# USB_Type_C_Connector_ESD.net
KiCad netlist of a schematic drawn in Altium Designer
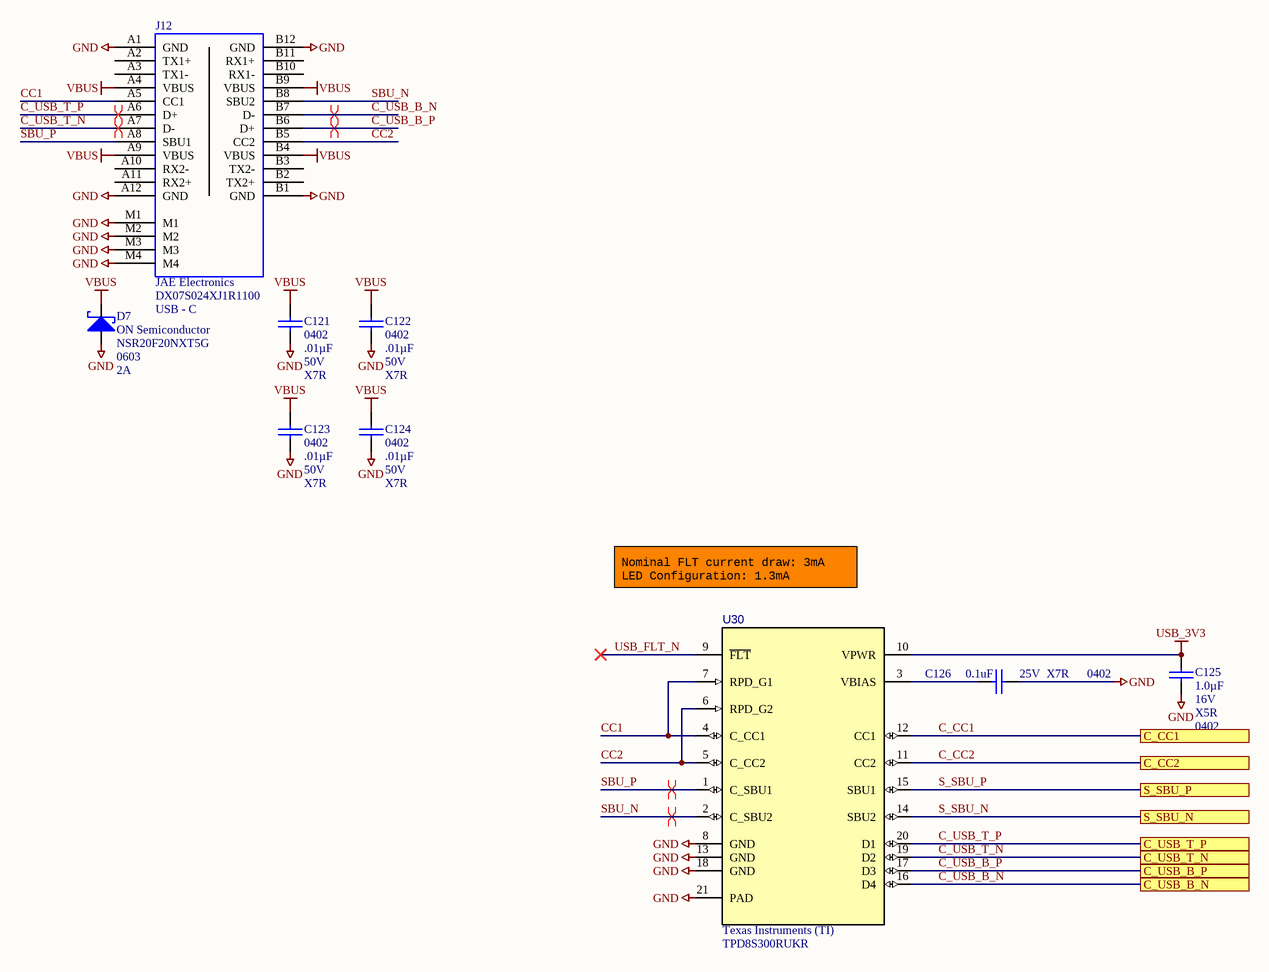
[diagram p0: USB Type C Connector ESD.SchDoc]

(export (version "E")
  (design (tool "Eeschema 10.0.6"))
  (components
    (comp (ref "C121")
      (value "10000pF")
      (footprint "C_0402")
      (description "CAP CERAMIC .01UF 50V X7R 0402")
      (fields
        (field (name "MANUFACTURER") "Murata Electronics North America")
        (field (name "MANUFACTURER PART NUMBER") "GRM155R71H103KA88D")
        (field (name "PACKAGE / CASE") "0402")
        (field (name "CAPACITANCE") ".01µF")
        (field (name "VOLTAGE - RATED") "50V")
        (field (name "TEMPERATURE COEFFICIENT") "X7R")
      )
      (libsource (lib "Main LibraryX") (part "C_0402_10000PF_50V"))
    )
    (comp (ref "C122")
      (value "10000pF")
      (footprint "C_0402")
      (description "CAP CERAMIC .01UF 50V X7R 0402")
      (fields
        (field (name "MANUFACTURER") "Murata Electronics North America")
        (field (name "MANUFACTURER PART NUMBER") "GRM155R71H103KA88D")
        (field (name "PACKAGE / CASE") "0402")
        (field (name "CAPACITANCE") ".01µF")
        (field (name "VOLTAGE - RATED") "50V")
        (field (name "TEMPERATURE COEFFICIENT") "X7R")
      )
      (libsource (lib "Main LibraryX") (part "C_0402_10000PF_50V"))
    )
    (comp (ref "C123")
      (value "10000pF")
      (footprint "C_0402")
      (description "CAP CERAMIC .01UF 50V X7R 0402")
      (fields
        (field (name "MANUFACTURER") "Murata Electronics North America")
        (field (name "MANUFACTURER PART NUMBER") "GRM155R71H103KA88D")
        (field (name "PACKAGE / CASE") "0402")
        (field (name "CAPACITANCE") ".01µF")
        (field (name "VOLTAGE - RATED") "50V")
        (field (name "TEMPERATURE COEFFICIENT") "X7R")
      )
      (libsource (lib "Main LibraryX") (part "C_0402_10000PF_50V"))
    )
    (comp (ref "C124")
      (value "10000pF")
      (footprint "C_0402")
      (description "CAP CERAMIC .01UF 50V X7R 0402")
      (fields
        (field (name "MANUFACTURER") "Murata Electronics North America")
        (field (name "MANUFACTURER PART NUMBER") "GRM155R71H103KA88D")
        (field (name "PACKAGE / CASE") "0402")
        (field (name "CAPACITANCE") ".01µF")
        (field (name "VOLTAGE - RATED") "50V")
        (field (name "TEMPERATURE COEFFICIENT") "X7R")
      )
      (libsource (lib "Main LibraryX") (part "C_0402_10000PF_50V"))
    )
    (comp (ref "C125")
      (value "1.0uF")
      (footprint "C_0402")
      (description "CAP CER 1.0UF 16V X5R 0402")
      (fields
        (field (name "TOLERANCE") "10%")
        (field (name "CAPACITANCE") "1.0µF")
        (field (name "VOLTAGE - RATED") "16V")
        (field (name "TEMPERATURE COEFFICIENT") "X5R")
        (field (name "PACKAGE / CASE") "0402")
        (field (name "VOLTAGE") "16V")
      )
      (libsource (lib "Main LibraryX") (part "C_0402_1.0UF_16V"))
    )
    (comp (ref "C126")
      (value "C_0402_0.1UF_25V")
      (footprint "C_0402")
      (description "CAP CER 0.1UF 25V X6S 0402")
      (fields
        (field (name "TOLERANCE") "10%")
        (field (name "CAPACITANCE") "0.1uF")
        (field (name "VOLTAGE - RATED") "25V")
        (field (name "TEMPERATURE COEFFICIENT") "X7R")
        (field (name "PACKAGE / CASE") "0402")
      )
      (libsource (lib "Cospan Design") (part "C_0402_0.1UF_25V"))
    )
    (comp (ref "D7")
      (value "D_SCHOTT_30V_2A_XDFN")
      (footprint "DSN2_0603")
      (description "Diode Schottky 30V 2A (DC) Surface Mount 2-DSN (1.6x.80)")
      (fields
        (field (name "MANUFACTURER") "ON Semiconductor")
        (field (name "MANUFACTURER PART NUMBER") "NSR20F20NXT5G")
        (field (name "CASE/PACKAGE") "0603")
        (field (name "AVERAGE RECTIFIED CURRENT") "2A")
      )
      (libsource (lib "Cospan Design") (part "D_SCHOTT_30V_2A_XDFN"))
    )
    (comp (ref "J12")
      (value "J_DX07S024XJ1R1100")
      (footprint "DX07S024XJ1R1100")
      (description "CONN RCPT USB C TOP MNT HYBRID")
      (fields
        (field (name "MANUFACTURER") "JAE Electronics")
        (field (name "MANUFACTURER PART NUMBER") "DX07S024XJ1R1100")
        (field (name "CONNECTOR TYPE") "USB - C")
      )
      (libsource (lib "Cospan Design") (part "J_DX07S024XJ1R1100"))
    )
    (comp (ref "U30")
      (value "U_TPD8S300RUK")
      (footprint "RUK0020B")
      (fields
        (field (name "MANUFACTURER") "Texas Instruments (TI)")
        (field (name "MANUFACTURER PART NUMBER") "TPD8S300RUKR")
      )
      (libsource (lib "Cospan Design") (part "U_TPD8S300RUK"))
    )
  )
  (nets
    (net (code "1") (name "/CC1") (class "Default")
      (node (ref "J12") (pin "A5") (pinfunction "CC1_A5") (pintype "passive"))
      (node (ref "U30") (pin "4") (pinfunction "C_CC1_4") (pintype "bidirectional"))
      (node (ref "U30") (pin "7") (pinfunction "RPD_G1_7") (pintype "input"))
    )
    (net (code "2") (name "/CC2") (class "Default")
      (node (ref "J12") (pin "B5") (pinfunction "CC2_B5") (pintype "passive"))
      (node (ref "U30") (pin "5") (pinfunction "C_CC2_5") (pintype "bidirectional"))
      (node (ref "U30") (pin "6") (pinfunction "RPD_G2_6") (pintype "input"))
    )
    (net (code "3") (name "/C_CC1") (class "Default")
      (node (ref "U30") (pin "12") (pinfunction "CC1_12") (pintype "bidirectional"))
    )
    (net (code "4") (name "/C_CC2") (class "Default")
      (node (ref "U30") (pin "11") (pinfunction "CC2_11") (pintype "bidirectional"))
    )
    (net (code "5") (name "/C_USB_B_N") (class "Default")
      (node (ref "J12") (pin "B7") (pinfunction "D-_B7") (pintype "passive"))
      (node (ref "U30") (pin "16") (pinfunction "D4_16") (pintype "bidirectional"))
    )
    (net (code "6") (name "/C_USB_B_P") (class "Default")
      (node (ref "J12") (pin "B6") (pinfunction "D+_B6") (pintype "passive"))
      (node (ref "U30") (pin "17") (pinfunction "D3_17") (pintype "bidirectional"))
    )
    (net (code "7") (name "/C_USB_T_N") (class "Default")
      (node (ref "J12") (pin "A7") (pinfunction "D-_A7") (pintype "passive"))
      (node (ref "U30") (pin "19") (pinfunction "D2_19") (pintype "bidirectional"))
    )
    (net (code "8") (name "/C_USB_T_P") (class "Default")
      (node (ref "J12") (pin "A6") (pinfunction "D+_A6") (pintype "passive"))
      (node (ref "U30") (pin "20") (pinfunction "D1_20") (pintype "bidirectional"))
    )
    (net (code "9") (name "/SBU_N") (class "Default")
      (node (ref "J12") (pin "B8") (pinfunction "SBU2_B8") (pintype "passive"))
      (node (ref "U30") (pin "2") (pinfunction "C_SBU2_2") (pintype "bidirectional"))
    )
    (net (code "10") (name "/SBU_P") (class "Default")
      (node (ref "J12") (pin "A8") (pinfunction "SBU1_A8") (pintype "passive"))
      (node (ref "U30") (pin "1") (pinfunction "C_SBU1_1") (pintype "bidirectional"))
    )
    (net (code "11") (name "/S_SBU_N") (class "Default")
      (node (ref "U30") (pin "14") (pinfunction "SBU2_14") (pintype "bidirectional"))
    )
    (net (code "12") (name "/S_SBU_P") (class "Default")
      (node (ref "U30") (pin "15") (pinfunction "SBU1_15") (pintype "bidirectional"))
    )
    (net (code "13") (name "/USB_FLT_N") (class "Default")
      (node (ref "U30") (pin "9") (pinfunction "FLT_9") (pintype "open_collector+no_connect"))
    )
    (net (code "14") (name "GND") (class "Default")
      (node (ref "C121") (pin "1") (pinfunction "1_1") (pintype "passive"))
      (node (ref "C122") (pin "1") (pinfunction "1_1") (pintype "passive"))
      (node (ref "C123") (pin "1") (pinfunction "1_1") (pintype "passive"))
      (node (ref "C124") (pin "1") (pinfunction "1_1") (pintype "passive"))
      (node (ref "C125") (pin "1") (pinfunction "1_1") (pintype "passive"))
      (node (ref "C126") (pin "1") (pinfunction "1_1") (pintype "passive"))
      (node (ref "D7") (pin "2") (pinfunction "A_2") (pintype "passive"))
      (node (ref "J12") (pin "A1") (pinfunction "GND_A1") (pintype "passive"))
      (node (ref "J12") (pin "A12") (pinfunction "GND_A12") (pintype "passive"))
      (node (ref "J12") (pin "B1") (pinfunction "GND_B1") (pintype "passive"))
      (node (ref "J12") (pin "B12") (pinfunction "GND_B12") (pintype "passive"))
      (node (ref "J12") (pin "M1") (pinfunction "M1_M1") (pintype "passive"))
      (node (ref "J12") (pin "M2") (pinfunction "M2_M2") (pintype "passive"))
      (node (ref "J12") (pin "M3") (pinfunction "M3_M3") (pintype "passive"))
      (node (ref "J12") (pin "M4") (pinfunction "M4_M4") (pintype "passive"))
      (node (ref "U30") (pin "13") (pinfunction "GND_13") (pintype "power_in"))
      (node (ref "U30") (pin "18") (pinfunction "GND_18") (pintype "power_in"))
      (node (ref "U30") (pin "21") (pinfunction "PAD_21") (pintype "power_in"))
      (node (ref "U30") (pin "8") (pinfunction "GND_8") (pintype "power_in"))
    )
    (net (code "15") (name "Net-(U30-VBIAS)") (class "Default")
      (node (ref "C126") (pin "2") (pinfunction "2_2") (pintype "passive"))
      (node (ref "U30") (pin "3") (pinfunction "VBIAS_3") (pintype "power_in"))
    )
    (net (code "16") (name "USB_3V3") (class "Default")
      (node (ref "C125") (pin "2") (pinfunction "2_2") (pintype "passive"))
      (node (ref "U30") (pin "10") (pinfunction "VPWR_10") (pintype "power_in"))
    )
    (net (code "17") (name "VBUS") (class "Default")
      (node (ref "C121") (pin "2") (pinfunction "2_2") (pintype "passive"))
      (node (ref "C122") (pin "2") (pinfunction "2_2") (pintype "passive"))
      (node (ref "C123") (pin "2") (pinfunction "2_2") (pintype "passive"))
      (node (ref "C124") (pin "2") (pinfunction "2_2") (pintype "passive"))
      (node (ref "D7") (pin "1") (pinfunction "C_1") (pintype "passive"))
      (node (ref "J12") (pin "A4") (pinfunction "VBUS_A4") (pintype "passive"))
      (node (ref "J12") (pin "A9") (pinfunction "VBUS_A9") (pintype "passive"))
      (node (ref "J12") (pin "B4") (pinfunction "VBUS_B4") (pintype "passive"))
      (node (ref "J12") (pin "B9") (pinfunction "VBUS_B9") (pintype "passive"))
    )
    (net (code "18") (name "unconnected-(J12-RX1+-PadB11)") (class "Default")
      (node (ref "J12") (pin "B11") (pinfunction "RX1+_B11") (pintype "passive"))
    )
    (net (code "19") (name "unconnected-(J12-RX1--PadB10)") (class "Default")
      (node (ref "J12") (pin "B10") (pinfunction "RX1-_B10") (pintype "passive"))
    )
    (net (code "20") (name "unconnected-(J12-RX2+-PadA11)") (class "Default")
      (node (ref "J12") (pin "A11") (pinfunction "RX2+_A11") (pintype "passive"))
    )
    (net (code "21") (name "unconnected-(J12-RX2--PadA10)") (class "Default")
      (node (ref "J12") (pin "A10") (pinfunction "RX2-_A10") (pintype "passive"))
    )
    (net (code "22") (name "unconnected-(J12-TX1+-PadA2)") (class "Default")
      (node (ref "J12") (pin "A2") (pinfunction "TX1+_A2") (pintype "passive"))
    )
    (net (code "23") (name "unconnected-(J12-TX1--PadA3)") (class "Default")
      (node (ref "J12") (pin "A3") (pinfunction "TX1-_A3") (pintype "passive"))
    )
    (net (code "24") (name "unconnected-(J12-TX2+-PadB2)") (class "Default")
      (node (ref "J12") (pin "B2") (pinfunction "TX2+_B2") (pintype "passive"))
    )
    (net (code "25") (name "unconnected-(J12-TX2--PadB3)") (class "Default")
      (node (ref "J12") (pin "B3") (pinfunction "TX2-_B3") (pintype "passive"))
    )
  )
)
